# Adafruit_TPL5110.net
KiCad netlist of a schematic drawn in EAGLE
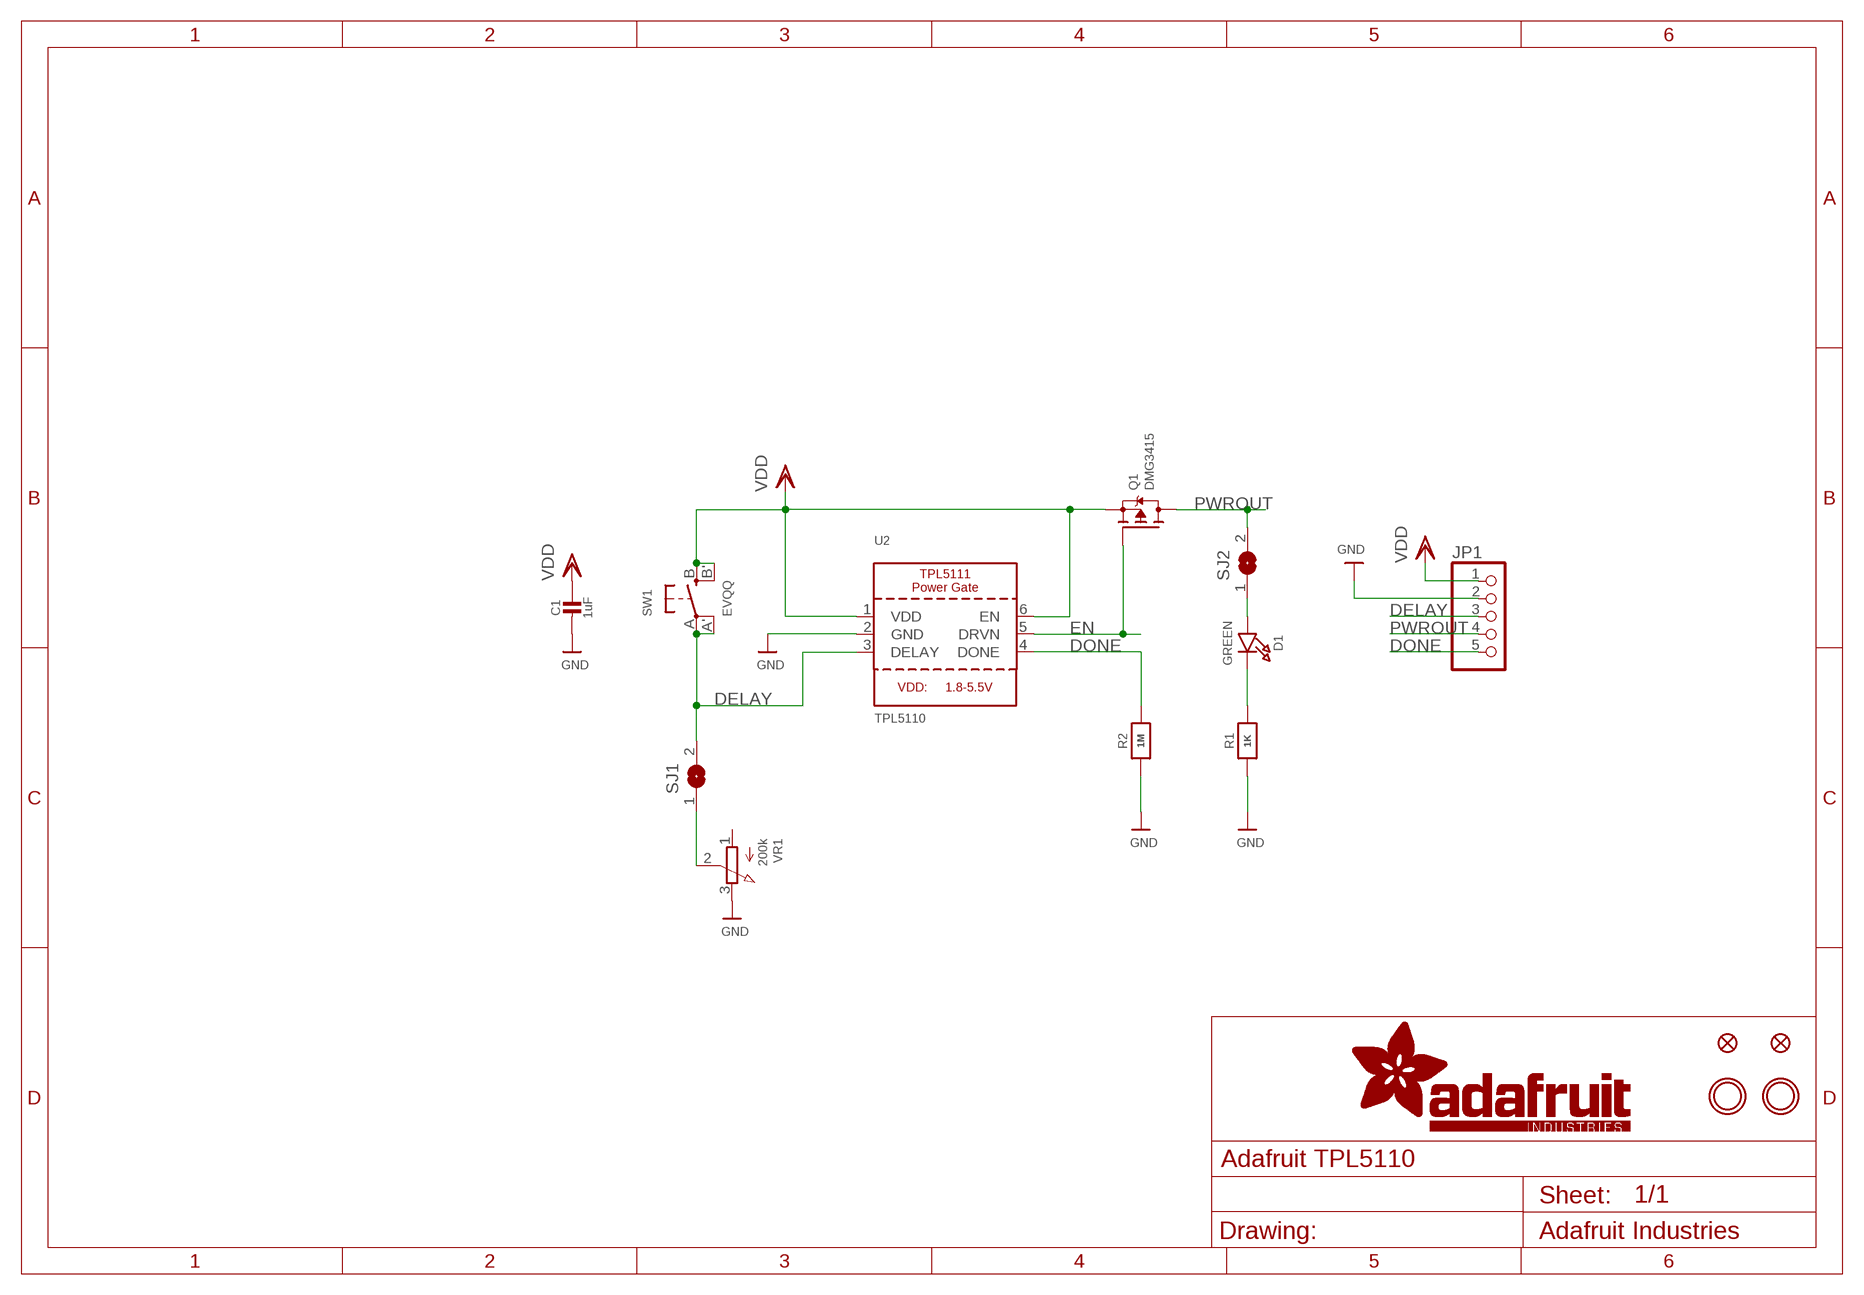
[diagram p0: schematic, sheet 1]

(export (version "E")
  (design (tool "Eeschema 10.0.6"))
  (components
    (comp (ref "C1")
      (value "1uF")
      (footprint "eagle-import:0805-NO")
      (libsource (lib "eagle-import") (part "CAP_CERAMIC0805-NOOUTLINE"))
    )
    (comp (ref "D1")
      (value "GREEN")
      (footprint "eagle-import:CHIPLED_0805_NOOUTLINE")
      (libsource (lib "eagle-import") (part "LED0805_NOOUTLINE"))
    )
    (comp (ref "FID1")
      (value "FIDUCIAL\"\"")
      (footprint "eagle-import:FIDUCIAL_1MM")
      (libsource (lib "eagle-import") (part "FIDUCIAL{dblquote}{dblquote}"))
    )
    (comp (ref "FID2")
      (value "FIDUCIAL\"\"")
      (footprint "eagle-import:FIDUCIAL_1MM")
      (libsource (lib "eagle-import") (part "FIDUCIAL{dblquote}{dblquote}"))
    )
    (comp (ref "JP1")
      (value "HEADER-1X570MIL")
      (footprint "eagle-import:1X05_ROUND_70")
      (libsource (lib "eagle-import") (part "HEADER-1X570MIL"))
    )
    (comp (ref "Q1")
      (value "DMG3415")
      (footprint "eagle-import:SOT23-WIDE")
      (libsource (lib "eagle-import") (part "MOSFET-PWIDE"))
    )
    (comp (ref "R1")
      (value "1K")
      (footprint "eagle-import:0805-NO")
      (libsource (lib "eagle-import") (part "RESISTOR0805_NOOUTLINE"))
    )
    (comp (ref "R2")
      (value "1M")
      (footprint "eagle-import:0805-NO")
      (libsource (lib "eagle-import") (part "RESISTOR0805_NOOUTLINE"))
    )
    (comp (ref "SJ1")
      (value "SOLDERJUMPERCLOSED")
      (footprint "eagle-import:SOLDERJUMPER_CLOSEDWIRE")
      (libsource (lib "eagle-import") (part "SOLDERJUMPERCLOSED"))
    )
    (comp (ref "SJ2")
      (value "SOLDERJUMPERCLOSED")
      (footprint "eagle-import:SOLDERJUMPER_CLOSEDWIRE")
      (libsource (lib "eagle-import") (part "SOLDERJUMPERCLOSED"))
    )
    (comp (ref "SW1")
      (value "EVQQ")
      (footprint "eagle-import:EVQ-Q2_SMALLER")
      (libsource (lib "eagle-import") (part "SWITCH_TACT_SMT_EVQQ2_SMALL"))
    )
    (comp (ref "U$7")
      (value "MOUNTINGHOLE2.5")
      (footprint "eagle-import:MOUNTINGHOLE_2.5_PLATED")
      (libsource (lib "eagle-import") (part "MOUNTINGHOLE2.5"))
    )
    (comp (ref "U$8")
      (value "MOUNTINGHOLE2.5")
      (footprint "eagle-import:MOUNTINGHOLE_2.5_PLATED")
      (libsource (lib "eagle-import") (part "MOUNTINGHOLE2.5"))
    )
    (comp (ref "U2")
      (value "TPL5110")
      (footprint "eagle-import:SOT23-6")
      (libsource (lib "eagle-import") (part "TPL5111"))
    )
    (comp (ref "VR1")
      (value "200k")
      (footprint "eagle-import:TRIMPOT_BOURNS_TC33X-2")
      (libsource (lib "eagle-import") (part "TRIMPOTTC33X-2"))
    )
  )
  (nets
    (net (code "1") (name "/DELAY") (class "Default")
      (node (ref "JP1") (pin "3") (pinfunction "3_3") (pintype "passive"))
      (node (ref "SJ1") (pin "2") (pinfunction "2_2") (pintype "passive"))
      (node (ref "SW1") (pin "A") (pinfunction "P_A") (pintype "passive"))
      (node (ref "SW1") (pin "A'") (pinfunction "P1_A'") (pintype "passive"))
      (node (ref "U2") (pin "3") (pinfunction "DELAY_3") (pintype "input"))
    )
    (net (code "2") (name "/DONE") (class "Default")
      (node (ref "JP1") (pin "5") (pinfunction "5_5") (pintype "passive"))
      (node (ref "R2") (pin "2") (pinfunction "2_2") (pintype "passive"))
      (node (ref "U2") (pin "4") (pinfunction "DONE_4") (pintype "input"))
    )
    (net (code "3") (name "/EN") (class "Default")
      (node (ref "Q1") (pin "1") (pinfunction "G_1") (pintype "passive"))
      (node (ref "U2") (pin "5") (pinfunction "DRVN_5") (pintype "output"))
    )
    (net (code "4") (name "/PWROUT") (class "Default")
      (node (ref "JP1") (pin "4") (pinfunction "4_4") (pintype "passive"))
      (node (ref "Q1") (pin "3") (pinfunction "D_3") (pintype "passive"))
      (node (ref "SJ2") (pin "2") (pinfunction "2_2") (pintype "passive"))
    )
    (net (code "5") (name "GND") (class "Default")
      (node (ref "C1") (pin "2") (pinfunction "2_2") (pintype "passive"))
      (node (ref "JP1") (pin "2") (pinfunction "2_2") (pintype "passive"))
      (node (ref "R1") (pin "1") (pinfunction "1_1") (pintype "passive"))
      (node (ref "R2") (pin "1") (pinfunction "1_1") (pintype "passive"))
      (node (ref "U2") (pin "2") (pinfunction "GND_2") (pintype "power_in"))
      (node (ref "VR1") (pin "3") (pinfunction "E_3") (pintype "passive"))
    )
    (net (code "6") (name "Net-(D1-PadA)") (class "Default")
      (node (ref "D1") (pin "A") (pinfunction "A_A") (pintype "passive"))
      (node (ref "SJ2") (pin "1") (pinfunction "1_1") (pintype "passive"))
    )
    (net (code "7") (name "Net-(D1-PadC)") (class "Default")
      (node (ref "D1") (pin "C") (pinfunction "C_C") (pintype "passive"))
      (node (ref "R1") (pin "2") (pinfunction "2_2") (pintype "passive"))
    )
    (net (code "8") (name "Net-(VR1-S)") (class "Default")
      (node (ref "SJ1") (pin "1") (pinfunction "1_1") (pintype "passive"))
      (node (ref "VR1") (pin "2") (pinfunction "S_2") (pintype "passive"))
    )
    (net (code "9") (name "VDD") (class "Default")
      (node (ref "C1") (pin "1") (pinfunction "1_1") (pintype "passive"))
      (node (ref "JP1") (pin "1") (pinfunction "1_1") (pintype "passive"))
      (node (ref "Q1") (pin "2") (pinfunction "S_2") (pintype "passive"))
      (node (ref "SW1") (pin "B") (pinfunction "S_B") (pintype "passive"))
      (node (ref "SW1") (pin "B'") (pinfunction "S1_B'") (pintype "passive"))
      (node (ref "U2") (pin "1") (pinfunction "VDD_1") (pintype "power_in"))
      (node (ref "U2") (pin "6") (pinfunction "EN_6") (pintype "input"))
    )
    (net (code "10") (name "unconnected-(VR1-A-Pad1)") (class "Default")
      (node (ref "VR1") (pin "1") (pinfunction "A_1") (pintype "passive"))
    )
  )
)
